# keycontrol.net
KiCad netlist of a schematic drawn in Altium Designer
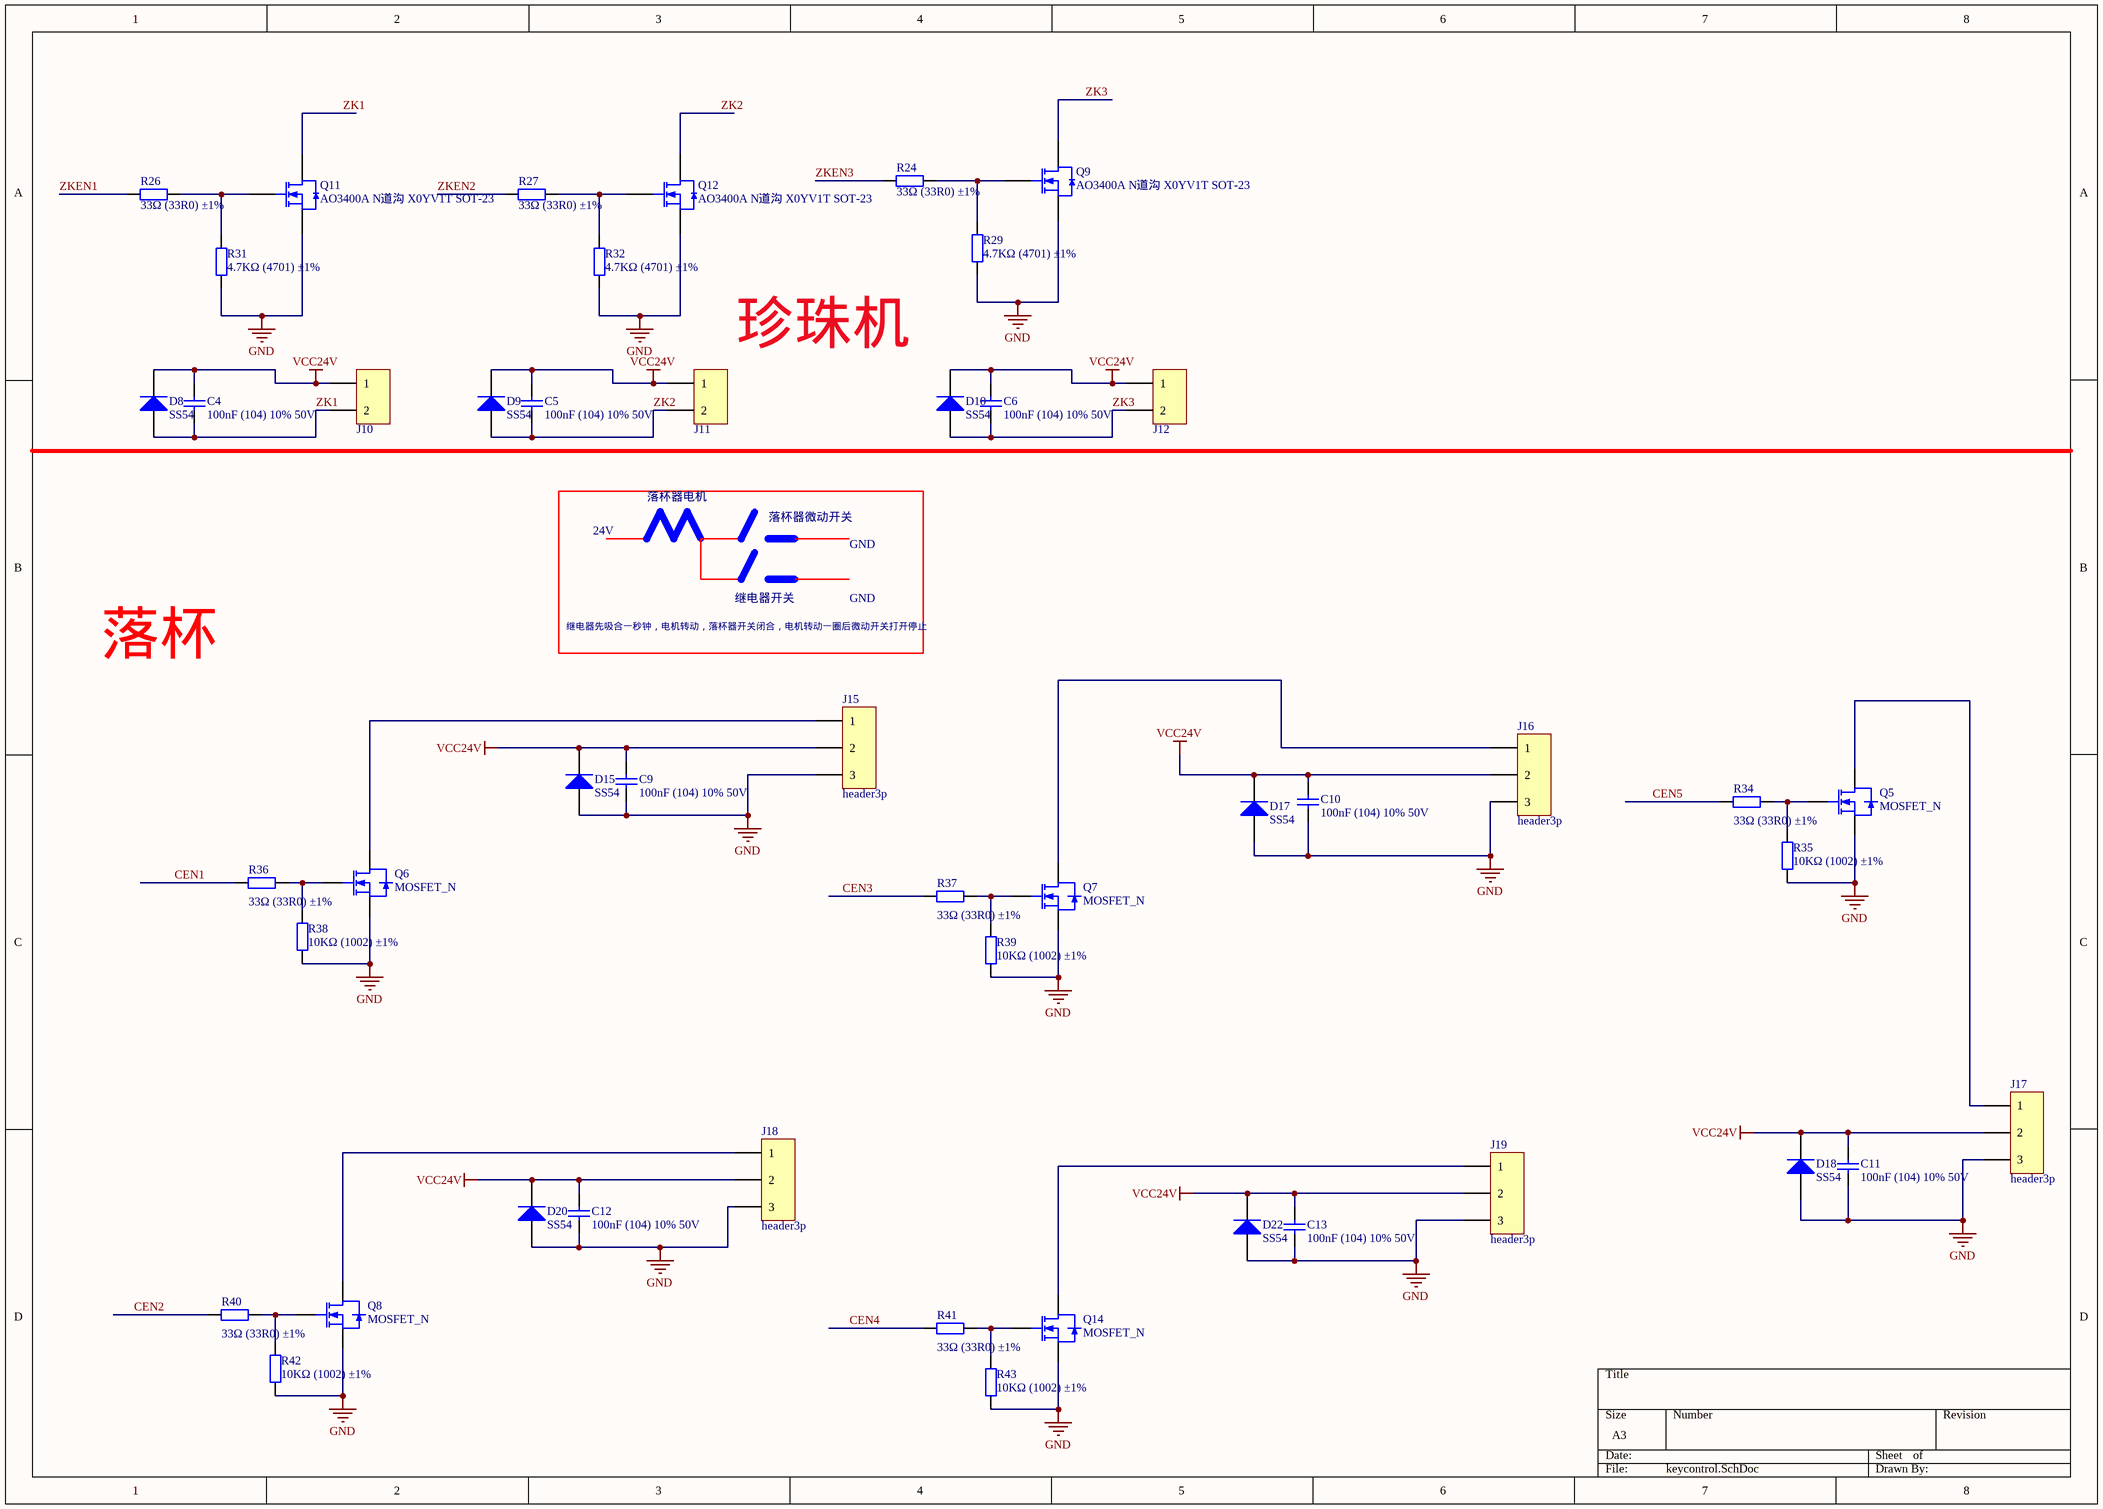
[diagram p0: keycontrol.SchDoc]

(export (version "E")
  (design (tool "Eeschema 10.0.6"))
  (components
    (comp (ref "C4")
      (value "100nF (104) 10% 50V")
      (footprint "0603_C")
      (description "贴片电容")
      (libsource (lib "AD封装2018.9.19Miscellaneous Devices LC") (part "0603 100nF (104) 10% 50V"))
    )
    (comp (ref "C5")
      (value "100nF (104) 10% 50V")
      (footprint "0603_C")
      (description "贴片电容")
      (libsource (lib "AD封装2018.9.19Miscellaneous Devices LC") (part "0603 100nF (104) 10% 50V"))
    )
    (comp (ref "C6")
      (value "100nF (104) 10% 50V")
      (footprint "0603_C")
      (description "贴片电容")
      (libsource (lib "AD封装2018.9.19Miscellaneous Devices LC") (part "0603 100nF (104) 10% 50V"))
    )
    (comp (ref "C9")
      (value "100nF (104) 10% 50V")
      (footprint "0603_C")
      (description "贴片电容")
      (libsource (lib "AD封装2018.9.19Miscellaneous Devices LC") (part "0603 100nF (104) 10% 50V"))
    )
    (comp (ref "C10")
      (value "100nF (104) 10% 50V")
      (footprint "0603_C")
      (description "贴片电容")
      (libsource (lib "AD封装2018.9.19Miscellaneous Devices LC") (part "0603 100nF (104) 10% 50V"))
    )
    (comp (ref "C11")
      (value "100nF (104) 10% 50V")
      (footprint "0603_C")
      (description "贴片电容")
      (libsource (lib "AD封装2018.9.19Miscellaneous Devices LC") (part "0603 100nF (104) 10% 50V"))
    )
    (comp (ref "C12")
      (value "100nF (104) 10% 50V")
      (footprint "0603_C")
      (description "贴片电容")
      (libsource (lib "AD封装2018.9.19Miscellaneous Devices LC") (part "0603 100nF (104) 10% 50V"))
    )
    (comp (ref "C13")
      (value "100nF (104) 10% 50V")
      (footprint "0603_C")
      (description "贴片电容")
      (libsource (lib "AD封装2018.9.19Miscellaneous Devices LC") (part "0603 100nF (104) 10% 50V"))
    )
    (comp (ref "D8")
      (value "SS54")
      (footprint "SMA(DO-214AC)_S1")
      (description "二极管")
      (libsource (lib "Diode") (part "SMA(DO-214AC) SS54"))
    )
    (comp (ref "D9")
      (value "SS54")
      (footprint "SMA(DO-214AC)_S1")
      (description "二极管")
      (libsource (lib "Diode") (part "SMA(DO-214AC) SS54"))
    )
    (comp (ref "D10")
      (value "SS54")
      (footprint "SMA(DO-214AC)_S1")
      (description "二极管")
      (libsource (lib "Diode") (part "SMA(DO-214AC) SS54"))
    )
    (comp (ref "D15")
      (value "SS54")
      (footprint "SMA(DO-214AC)_S1")
      (description "二极管")
      (libsource (lib "Diode") (part "SMA(DO-214AC) SS54"))
    )
    (comp (ref "D17")
      (value "SS54")
      (footprint "SMA(DO-214AC)_S1")
      (description "二极管")
      (libsource (lib "Diode") (part "SMA(DO-214AC) SS54"))
    )
    (comp (ref "D18")
      (value "SS54")
      (footprint "SMA(DO-214AC)_S1")
      (description "二极管")
      (libsource (lib "Diode") (part "SMA(DO-214AC) SS54"))
    )
    (comp (ref "D20")
      (value "SS54")
      (footprint "SMA(DO-214AC)_S1")
      (description "二极管")
      (libsource (lib "Diode") (part "SMA(DO-214AC) SS54"))
    )
    (comp (ref "D22")
      (value "SS54")
      (footprint "SMA(DO-214AC)_S1")
      (description "二极管")
      (libsource (lib "Diode") (part "SMA(DO-214AC) SS54"))
    )
    (comp (ref "J10") (value "MOTOR") (footprint "XH-2P") (libsource (lib "我的集成库") (part "header2")))
    (comp (ref "J11") (value "MOTOR") (footprint "XH-2P") (libsource (lib "我的集成库") (part "header2")))
    (comp (ref "J12") (value "MOTOR") (footprint "XH-2P") (libsource (lib "我的集成库") (part "header2")))
    (comp (ref "J15") (value "header3p") (footprint "XH-3") (libsource (lib "我的集成库") (part "header3p")))
    (comp (ref "J16") (value "header3p") (footprint "XH-3") (libsource (lib "我的集成库") (part "header3p")))
    (comp (ref "J17") (value "header3p") (footprint "XH-3") (libsource (lib "我的集成库") (part "header3p")))
    (comp (ref "J18") (value "header3p") (footprint "XH-3") (libsource (lib "我的集成库") (part "header3p")))
    (comp (ref "J19") (value "header3p") (footprint "XH-3") (libsource (lib "我的集成库") (part "header3p")))
    (comp (ref "Q5") (value "MOSFET_N") (footprint "TO-252-2") (libsource (lib "我的集成库") (part "MOSFET_N")))
    (comp (ref "Q6") (value "MOSFET_N") (footprint "TO-252-2") (libsource (lib "我的集成库") (part "MOSFET_N")))
    (comp (ref "Q7") (value "MOSFET_N") (footprint "TO-252-2") (libsource (lib "我的集成库") (part "MOSFET_N")))
    (comp (ref "Q8") (value "MOSFET_N") (footprint "TO-252-2") (libsource (lib "我的集成库") (part "MOSFET_N")))
    (comp (ref "Q9")
      (value "AO3400A N道沟 X0YV1T SOT-23")
      (footprint "SOT-23-3L")
      (description "MOS(场效应管)")
      (libsource (lib "AD封装2018.9.19Miscellaneous Devices LC") (part "AO3400A N道沟 X0YV1T SOT-23"))
    )
    (comp (ref "Q11")
      (value "AO3400A N道沟 X0YV1T SOT-23")
      (footprint "SOT-23-3L")
      (description "MOS(场效应管)")
      (libsource (lib "AD封装2018.9.19Miscellaneous Devices LC") (part "AO3400A N道沟 X0YV1T SOT-23"))
    )
    (comp (ref "Q12")
      (value "AO3400A N道沟 X0YV1T SOT-23")
      (footprint "SOT-23-3L")
      (description "MOS(场效应管)")
      (libsource (lib "AD封装2018.9.19Miscellaneous Devices LC") (part "AO3400A N道沟 X0YV1T SOT-23"))
    )
    (comp (ref "Q14") (value "MOSFET_N") (footprint "TO-252-2") (libsource (lib "我的集成库") (part "MOSFET_N")))
    (comp (ref "R24")
      (value "33Ω (33R0) ±1%")
      (footprint "0603_R")
      (description "贴片电阻")
      (libsource (lib "AD封装2018.9.19Miscellaneous Devices LC") (part "0603 33Ω (33R0) 1%"))
    )
    (comp (ref "R26")
      (value "33Ω (33R0) ±1%")
      (footprint "0603_R")
      (description "贴片电阻")
      (libsource (lib "AD封装2018.9.19Miscellaneous Devices LC") (part "0603 33Ω (33R0) 1%"))
    )
    (comp (ref "R27")
      (value "33Ω (33R0) ±1%")
      (footprint "0603_R")
      (description "贴片电阻")
      (libsource (lib "AD封装2018.9.19Miscellaneous Devices LC") (part "0603 33Ω (33R0) 1%"))
    )
    (comp (ref "R29")
      (value "4.7KΩ (4701) ±1%")
      (footprint "0603_R")
      (description "贴片电阻")
      (libsource (lib "AD封装2018.9.19Miscellaneous Devices LC") (part "0603 4.7KΩ (4701) 1%"))
    )
    (comp (ref "R31")
      (value "4.7KΩ (4701) ±1%")
      (footprint "0603_R")
      (description "贴片电阻")
      (libsource (lib "AD封装2018.9.19Miscellaneous Devices LC") (part "0603 4.7KΩ (4701) 1%"))
    )
    (comp (ref "R32")
      (value "4.7KΩ (4701) ±1%")
      (footprint "0603_R")
      (description "贴片电阻")
      (libsource (lib "AD封装2018.9.19Miscellaneous Devices LC") (part "0603 4.7KΩ (4701) 1%"))
    )
    (comp (ref "R34")
      (value "33Ω (33R0) ±1%")
      (footprint "0603_R")
      (description "贴片电阻")
      (libsource (lib "AD封装2018.9.19Miscellaneous Devices LC") (part "0603 33Ω (33R0) 1%"))
    )
    (comp (ref "R35")
      (value "10KΩ (1002) ±1%")
      (footprint "0603_R")
      (description "贴片电阻")
      (libsource (lib "AD封装2018.9.19Miscellaneous Devices LC") (part "0603 10KΩ (1002) 1%"))
    )
    (comp (ref "R36")
      (value "33Ω (33R0) ±1%")
      (footprint "0603_R")
      (description "贴片电阻")
      (libsource (lib "AD封装2018.9.19Miscellaneous Devices LC") (part "0603 33Ω (33R0) 1%"))
    )
    (comp (ref "R37")
      (value "33Ω (33R0) ±1%")
      (footprint "0603_R")
      (description "贴片电阻")
      (libsource (lib "AD封装2018.9.19Miscellaneous Devices LC") (part "0603 33Ω (33R0) 1%"))
    )
    (comp (ref "R38")
      (value "10KΩ (1002) ±1%")
      (footprint "0603_R")
      (description "贴片电阻")
      (libsource (lib "AD封装2018.9.19Miscellaneous Devices LC") (part "0603 10KΩ (1002) 1%"))
    )
    (comp (ref "R39")
      (value "10KΩ (1002) ±1%")
      (footprint "0603_R")
      (description "贴片电阻")
      (libsource (lib "AD封装2018.9.19Miscellaneous Devices LC") (part "0603 10KΩ (1002) 1%"))
    )
    (comp (ref "R40")
      (value "33Ω (33R0) ±1%")
      (footprint "0603_R")
      (description "贴片电阻")
      (libsource (lib "AD封装2018.9.19Miscellaneous Devices LC") (part "0603 33Ω (33R0) 1%"))
    )
    (comp (ref "R41")
      (value "33Ω (33R0) ±1%")
      (footprint "0603_R")
      (description "贴片电阻")
      (libsource (lib "AD封装2018.9.19Miscellaneous Devices LC") (part "0603 33Ω (33R0) 1%"))
    )
    (comp (ref "R42")
      (value "10KΩ (1002) ±1%")
      (footprint "0603_R")
      (description "贴片电阻")
      (libsource (lib "AD封装2018.9.19Miscellaneous Devices LC") (part "0603 10KΩ (1002) 1%"))
    )
    (comp (ref "R43")
      (value "10KΩ (1002) ±1%")
      (footprint "0603_R")
      (description "贴片电阻")
      (libsource (lib "AD封装2018.9.19Miscellaneous Devices LC") (part "0603 10KΩ (1002) 1%"))
    )
  )
  (nets
    (net (code "1") (name "/CEN1") (class "Default")
      (node (ref "R36") (pin "1") (pinfunction "1_1") (pintype "passive"))
    )
    (net (code "2") (name "/CEN2") (class "Default")
      (node (ref "R40") (pin "1") (pinfunction "1_1") (pintype "passive"))
    )
    (net (code "3") (name "/CEN3") (class "Default")
      (node (ref "R37") (pin "1") (pinfunction "1_1") (pintype "passive"))
    )
    (net (code "4") (name "/CEN4") (class "Default")
      (node (ref "R41") (pin "1") (pinfunction "1_1") (pintype "passive"))
    )
    (net (code "5") (name "/CEN5") (class "Default")
      (node (ref "R34") (pin "1") (pinfunction "1_1") (pintype "passive"))
    )
    (net (code "6") (name "/ZK1") (class "Default")
      (node (ref "C4") (pin "1") (pinfunction "1_1") (pintype "passive"))
      (node (ref "D8") (pin "1") (pinfunction "A_1") (pintype "passive"))
      (node (ref "J10") (pin "2") (pinfunction "2_2") (pintype "passive"))
      (node (ref "Q11") (pin "3") (pinfunction "D_3") (pintype "passive"))
    )
    (net (code "7") (name "/ZK2") (class "Default")
      (node (ref "C5") (pin "1") (pinfunction "1_1") (pintype "passive"))
      (node (ref "D9") (pin "1") (pinfunction "A_1") (pintype "passive"))
      (node (ref "J11") (pin "2") (pinfunction "2_2") (pintype "passive"))
      (node (ref "Q12") (pin "3") (pinfunction "D_3") (pintype "passive"))
    )
    (net (code "8") (name "/ZK3") (class "Default")
      (node (ref "C6") (pin "1") (pinfunction "1_1") (pintype "passive"))
      (node (ref "D10") (pin "1") (pinfunction "A_1") (pintype "passive"))
      (node (ref "J12") (pin "2") (pinfunction "2_2") (pintype "passive"))
      (node (ref "Q9") (pin "3") (pinfunction "D_3") (pintype "passive"))
    )
    (net (code "9") (name "/ZKEN1") (class "Default")
      (node (ref "R26") (pin "1") (pinfunction "1_1") (pintype "passive"))
    )
    (net (code "10") (name "/ZKEN2") (class "Default")
      (node (ref "R27") (pin "1") (pinfunction "1_1") (pintype "passive"))
    )
    (net (code "11") (name "/ZKEN3") (class "Default")
      (node (ref "R24") (pin "1") (pinfunction "1_1") (pintype "passive"))
    )
    (net (code "12") (name "GND") (class "Default")
      (node (ref "C10") (pin "1") (pinfunction "1_1") (pintype "passive"))
      (node (ref "C11") (pin "1") (pinfunction "1_1") (pintype "passive"))
      (node (ref "C12") (pin "1") (pinfunction "1_1") (pintype "passive"))
      (node (ref "C13") (pin "1") (pinfunction "1_1") (pintype "passive"))
      (node (ref "C9") (pin "1") (pinfunction "1_1") (pintype "passive"))
      (node (ref "D15") (pin "1") (pinfunction "A_1") (pintype "passive"))
      (node (ref "D17") (pin "1") (pinfunction "A_1") (pintype "passive"))
      (node (ref "D18") (pin "1") (pinfunction "A_1") (pintype "passive"))
      (node (ref "D20") (pin "1") (pinfunction "A_1") (pintype "passive"))
      (node (ref "D22") (pin "1") (pinfunction "A_1") (pintype "passive"))
      (node (ref "J15") (pin "3") (pinfunction "3_3") (pintype "passive"))
      (node (ref "J16") (pin "3") (pinfunction "3_3") (pintype "passive"))
      (node (ref "J17") (pin "3") (pinfunction "3_3") (pintype "passive"))
      (node (ref "J18") (pin "3") (pinfunction "3_3") (pintype "passive"))
      (node (ref "J19") (pin "3") (pinfunction "3_3") (pintype "passive"))
      (node (ref "Q11") (pin "2") (pinfunction "S_2") (pintype "passive"))
      (node (ref "Q12") (pin "2") (pinfunction "S_2") (pintype "passive"))
      (node (ref "Q14") (pin "3") (pinfunction "S_3") (pintype "passive"))
      (node (ref "Q5") (pin "3") (pinfunction "S_3") (pintype "passive"))
      (node (ref "Q6") (pin "3") (pinfunction "S_3") (pintype "passive"))
      (node (ref "Q7") (pin "3") (pinfunction "S_3") (pintype "passive"))
      (node (ref "Q8") (pin "3") (pinfunction "S_3") (pintype "passive"))
      (node (ref "Q9") (pin "2") (pinfunction "S_2") (pintype "passive"))
      (node (ref "R29") (pin "1") (pinfunction "1_1") (pintype "passive"))
      (node (ref "R31") (pin "1") (pinfunction "1_1") (pintype "passive"))
      (node (ref "R32") (pin "1") (pinfunction "1_1") (pintype "passive"))
      (node (ref "R35") (pin "1") (pinfunction "1_1") (pintype "passive"))
      (node (ref "R38") (pin "1") (pinfunction "1_1") (pintype "passive"))
      (node (ref "R39") (pin "1") (pinfunction "1_1") (pintype "passive"))
      (node (ref "R42") (pin "1") (pinfunction "1_1") (pintype "passive"))
      (node (ref "R43") (pin "1") (pinfunction "1_1") (pintype "passive"))
    )
    (net (code "13") (name "Net-(Q5-D)") (class "Default")
      (node (ref "J17") (pin "1") (pinfunction "1_1") (pintype "passive"))
      (node (ref "Q5") (pin "2") (pinfunction "D_2") (pintype "passive"))
    )
    (net (code "14") (name "Net-(Q5-G)") (class "Default")
      (node (ref "Q5") (pin "1") (pinfunction "G_1") (pintype "passive"))
      (node (ref "R34") (pin "2") (pinfunction "2_2") (pintype "passive"))
      (node (ref "R35") (pin "2") (pinfunction "2_2") (pintype "passive"))
    )
    (net (code "15") (name "Net-(Q6-D)") (class "Default")
      (node (ref "J15") (pin "1") (pinfunction "1_1") (pintype "passive"))
      (node (ref "Q6") (pin "2") (pinfunction "D_2") (pintype "passive"))
    )
    (net (code "16") (name "Net-(Q6-G)") (class "Default")
      (node (ref "Q6") (pin "1") (pinfunction "G_1") (pintype "passive"))
      (node (ref "R36") (pin "2") (pinfunction "2_2") (pintype "passive"))
      (node (ref "R38") (pin "2") (pinfunction "2_2") (pintype "passive"))
    )
    (net (code "17") (name "Net-(Q7-D)") (class "Default")
      (node (ref "J16") (pin "1") (pinfunction "1_1") (pintype "passive"))
      (node (ref "Q7") (pin "2") (pinfunction "D_2") (pintype "passive"))
    )
    (net (code "18") (name "Net-(Q7-G)") (class "Default")
      (node (ref "Q7") (pin "1") (pinfunction "G_1") (pintype "passive"))
      (node (ref "R37") (pin "2") (pinfunction "2_2") (pintype "passive"))
      (node (ref "R39") (pin "2") (pinfunction "2_2") (pintype "passive"))
    )
    (net (code "19") (name "Net-(Q8-D)") (class "Default")
      (node (ref "J18") (pin "1") (pinfunction "1_1") (pintype "passive"))
      (node (ref "Q8") (pin "2") (pinfunction "D_2") (pintype "passive"))
    )
    (net (code "20") (name "Net-(Q8-G)") (class "Default")
      (node (ref "Q8") (pin "1") (pinfunction "G_1") (pintype "passive"))
      (node (ref "R40") (pin "2") (pinfunction "2_2") (pintype "passive"))
      (node (ref "R42") (pin "2") (pinfunction "2_2") (pintype "passive"))
    )
    (net (code "21") (name "Net-(Q9-G)") (class "Default")
      (node (ref "Q9") (pin "1") (pinfunction "G_1") (pintype "passive"))
      (node (ref "R24") (pin "2") (pinfunction "2_2") (pintype "passive"))
      (node (ref "R29") (pin "2") (pinfunction "2_2") (pintype "passive"))
    )
    (net (code "22") (name "Net-(Q11-G)") (class "Default")
      (node (ref "Q11") (pin "1") (pinfunction "G_1") (pintype "passive"))
      (node (ref "R26") (pin "2") (pinfunction "2_2") (pintype "passive"))
      (node (ref "R31") (pin "2") (pinfunction "2_2") (pintype "passive"))
    )
    (net (code "23") (name "Net-(Q12-G)") (class "Default")
      (node (ref "Q12") (pin "1") (pinfunction "G_1") (pintype "passive"))
      (node (ref "R27") (pin "2") (pinfunction "2_2") (pintype "passive"))
      (node (ref "R32") (pin "2") (pinfunction "2_2") (pintype "passive"))
    )
    (net (code "24") (name "Net-(Q14-D)") (class "Default")
      (node (ref "J19") (pin "1") (pinfunction "1_1") (pintype "passive"))
      (node (ref "Q14") (pin "2") (pinfunction "D_2") (pintype "passive"))
    )
    (net (code "25") (name "Net-(Q14-G)") (class "Default")
      (node (ref "Q14") (pin "1") (pinfunction "G_1") (pintype "passive"))
      (node (ref "R41") (pin "2") (pinfunction "2_2") (pintype "passive"))
      (node (ref "R43") (pin "2") (pinfunction "2_2") (pintype "passive"))
    )
    (net (code "26") (name "VCC24V") (class "Default")
      (node (ref "C10") (pin "2") (pinfunction "2_2") (pintype "passive"))
      (node (ref "C11") (pin "2") (pinfunction "2_2") (pintype "passive"))
      (node (ref "C12") (pin "2") (pinfunction "2_2") (pintype "passive"))
      (node (ref "C13") (pin "2") (pinfunction "2_2") (pintype "passive"))
      (node (ref "C4") (pin "2") (pinfunction "2_2") (pintype "passive"))
      (node (ref "C5") (pin "2") (pinfunction "2_2") (pintype "passive"))
      (node (ref "C6") (pin "2") (pinfunction "2_2") (pintype "passive"))
      (node (ref "C9") (pin "2") (pinfunction "2_2") (pintype "passive"))
      (node (ref "D10") (pin "2") (pinfunction "K_2") (pintype "passive"))
      (node (ref "D15") (pin "2") (pinfunction "K_2") (pintype "passive"))
      (node (ref "D17") (pin "2") (pinfunction "K_2") (pintype "passive"))
      (node (ref "D18") (pin "2") (pinfunction "K_2") (pintype "passive"))
      (node (ref "D20") (pin "2") (pinfunction "K_2") (pintype "passive"))
      (node (ref "D22") (pin "2") (pinfunction "K_2") (pintype "passive"))
      (node (ref "D8") (pin "2") (pinfunction "K_2") (pintype "passive"))
      (node (ref "D9") (pin "2") (pinfunction "K_2") (pintype "passive"))
      (node (ref "J10") (pin "1") (pinfunction "1_1") (pintype "passive"))
      (node (ref "J11") (pin "1") (pinfunction "1_1") (pintype "passive"))
      (node (ref "J12") (pin "1") (pinfunction "1_1") (pintype "passive"))
      (node (ref "J15") (pin "2") (pinfunction "2_2") (pintype "passive"))
      (node (ref "J16") (pin "2") (pinfunction "2_2") (pintype "passive"))
      (node (ref "J17") (pin "2") (pinfunction "2_2") (pintype "passive"))
      (node (ref "J18") (pin "2") (pinfunction "2_2") (pintype "passive"))
      (node (ref "J19") (pin "2") (pinfunction "2_2") (pintype "passive"))
    )
  )
)
